# BeatlePad.net
KiCad netlist of a schematic drawn in EAGLE
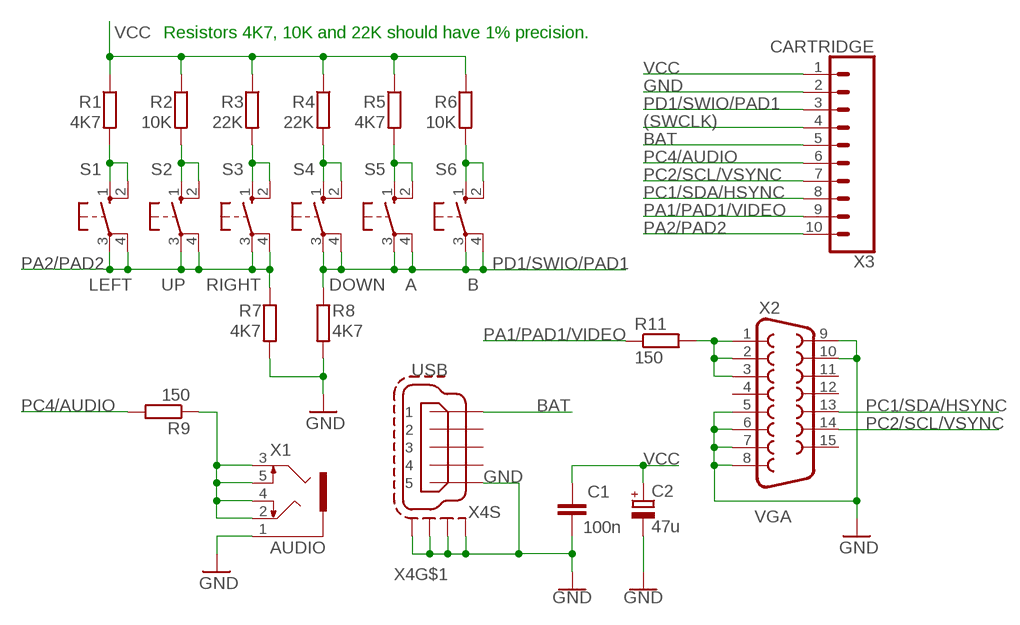
[diagram p0: schematic, sheet 1]

(export (version "E")
  (design (tool "Eeschema 10.0.6"))
  (components
    (comp (ref "C1")
      (value "100n")
      (footprint "eagle-import:C025-024X044")
      (libsource (lib "eagle-import") (part "C-EU025-024X044"))
    )
    (comp (ref "C2")
      (value "47u")
      (footprint "eagle-import:E2-4")
      (libsource (lib "eagle-import") (part "CPOL-EUE2-4"))
    )
    (comp (ref "R1")
      (value "4K7")
      (footprint "eagle-import:0204V")
      (libsource (lib "eagle-import") (part "R-EU_0204/2V"))
    )
    (comp (ref "R2")
      (value "10K")
      (footprint "eagle-import:0204V")
      (libsource (lib "eagle-import") (part "R-EU_0204/2V"))
    )
    (comp (ref "R3")
      (value "22K")
      (footprint "eagle-import:0204V")
      (libsource (lib "eagle-import") (part "R-EU_0204/2V"))
    )
    (comp (ref "R4")
      (value "22K")
      (footprint "eagle-import:0204V")
      (libsource (lib "eagle-import") (part "R-EU_0204/2V"))
    )
    (comp (ref "R5")
      (value "4K7")
      (footprint "eagle-import:0204V")
      (libsource (lib "eagle-import") (part "R-EU_0204/2V"))
    )
    (comp (ref "R6")
      (value "10K")
      (footprint "eagle-import:0204V")
      (libsource (lib "eagle-import") (part "R-EU_0204/2V"))
    )
    (comp (ref "R7")
      (value "4K7")
      (footprint "eagle-import:0204_5")
      (libsource (lib "eagle-import") (part "R-EU_0204/5"))
    )
    (comp (ref "R8")
      (value "4K7")
      (footprint "eagle-import:0204V")
      (libsource (lib "eagle-import") (part "R-EU_0204/2V"))
    )
    (comp (ref "R9")
      (value "150")
      (footprint "eagle-import:0204_5")
      (libsource (lib "eagle-import") (part "R-EU_0204/5"))
    )
    (comp (ref "R11")
      (value "150")
      (footprint "eagle-import:0204_5")
      (libsource (lib "eagle-import") (part "R-EU_0204/5"))
    )
    (comp (ref "S1")
      (value "LEFT")
      (footprint "eagle-import:B3F-10XXB")
      (libsource (lib "eagle-import") (part "10-XXB3F-10XXB"))
    )
    (comp (ref "S2")
      (value "UP")
      (footprint "eagle-import:B3F-10XXB")
      (libsource (lib "eagle-import") (part "10-XXB3F-10XXB"))
    )
    (comp (ref "S3")
      (value "RIGHT")
      (footprint "eagle-import:B3F-10XXB")
      (libsource (lib "eagle-import") (part "10-XXB3F-10XXB"))
    )
    (comp (ref "S4")
      (value "DOWN")
      (footprint "eagle-import:B3F-10XXB")
      (libsource (lib "eagle-import") (part "10-XXB3F-10XXB"))
    )
    (comp (ref "S5")
      (value "A")
      (footprint "eagle-import:B3F-10XXB")
      (libsource (lib "eagle-import") (part "10-XXB3F-10XXB"))
    )
    (comp (ref "S6")
      (value "B")
      (footprint "eagle-import:B3F-10XXB")
      (libsource (lib "eagle-import") (part "10-XXB3F-10XXB"))
    )
    (comp (ref "X1")
      (value "AUDIO")
      (footprint "eagle-import:1503_09")
      (libsource (lib "eagle-import") (part "1503_09"))
    )
    (comp (ref "X2")
      (value "VGA")
      (footprint "eagle-import:HDF15H")
      (libsource (lib "eagle-import") (part "F15HDH"))
    )
    (comp (ref "X3")
      (value "CARTRIDGE")
      (footprint "eagle-import:1X10_LONGPADS")
      (libsource (lib "eagle-import") (part "CONN_10"))
    )
    (comp (ref "X4")
      (value "USB")
      (footprint "eagle-import:32005-201")
      (libsource (lib "eagle-import") (part "MINI-USB-SCHIELD-32005-201"))
    )
  )
  (nets
    (net (code "1") (name "/(SWCLK)") (class "Default")
      (node (ref "X3") (pin "4") (pinfunction "4_4") (pintype "passive"))
    )
    (net (code "2") (name "/BAT") (class "Default")
      (node (ref "X3") (pin "5") (pinfunction "5_5") (pintype "passive"))
      (node (ref "X4") (pin "1") (pinfunction "1_1") (pintype "passive"))
    )
    (net (code "3") (name "/PA1{slash}PAD1{slash}VIDEO") (class "Default")
      (node (ref "R11") (pin "1") (pinfunction "1_1") (pintype "passive"))
      (node (ref "X3") (pin "9") (pinfunction "9_9") (pintype "passive"))
    )
    (net (code "4") (name "/PA2{slash}PAD2") (class "Default")
      (node (ref "R7") (pin "1") (pinfunction "1_1") (pintype "passive"))
      (node (ref "S1") (pin "3") (pinfunction "P_3") (pintype "passive"))
      (node (ref "S1") (pin "4") (pinfunction "P1_4") (pintype "passive"))
      (node (ref "S2") (pin "3") (pinfunction "P_3") (pintype "passive"))
      (node (ref "S2") (pin "4") (pinfunction "P1_4") (pintype "passive"))
      (node (ref "S3") (pin "3") (pinfunction "P_3") (pintype "passive"))
      (node (ref "S3") (pin "4") (pinfunction "P1_4") (pintype "passive"))
      (node (ref "X3") (pin "10") (pinfunction "10_10") (pintype "passive"))
    )
    (net (code "5") (name "/PC1{slash}SDA{slash}HSYNC") (class "Default")
      (node (ref "X2") (pin "13") (pinfunction "13_13") (pintype "passive"))
      (node (ref "X3") (pin "8") (pinfunction "8_8") (pintype "passive"))
    )
    (net (code "6") (name "/PC2{slash}SCL{slash}VSYNC") (class "Default")
      (node (ref "X2") (pin "14") (pinfunction "14_14") (pintype "passive"))
      (node (ref "X3") (pin "7") (pinfunction "7_7") (pintype "passive"))
    )
    (net (code "7") (name "/PC4{slash}AUDIO") (class "Default")
      (node (ref "R9") (pin "2") (pinfunction "2_2") (pintype "passive"))
      (node (ref "X3") (pin "6") (pinfunction "6_6") (pintype "passive"))
    )
    (net (code "8") (name "/PD1{slash}SWIO{slash}PAD1") (class "Default")
      (node (ref "R8") (pin "1") (pinfunction "1_1") (pintype "passive"))
      (node (ref "S4") (pin "3") (pinfunction "P_3") (pintype "passive"))
      (node (ref "S4") (pin "4") (pinfunction "P1_4") (pintype "passive"))
      (node (ref "S5") (pin "3") (pinfunction "P_3") (pintype "passive"))
      (node (ref "S5") (pin "4") (pinfunction "P1_4") (pintype "passive"))
      (node (ref "S6") (pin "3") (pinfunction "P_3") (pintype "passive"))
      (node (ref "S6") (pin "4") (pinfunction "P1_4") (pintype "passive"))
      (node (ref "X3") (pin "3") (pinfunction "3_3") (pintype "passive"))
    )
    (net (code "9") (name "/VCC") (class "Default")
      (node (ref "C1") (pin "1") (pinfunction "1_1") (pintype "passive"))
      (node (ref "C2") (pin "+") (pinfunction "+_+") (pintype "passive"))
      (node (ref "R1") (pin "1") (pinfunction "1_1") (pintype "passive"))
      (node (ref "R2") (pin "1") (pinfunction "1_1") (pintype "passive"))
      (node (ref "R3") (pin "1") (pinfunction "1_1") (pintype "passive"))
      (node (ref "R4") (pin "1") (pinfunction "1_1") (pintype "passive"))
      (node (ref "R5") (pin "1") (pinfunction "1_1") (pintype "passive"))
      (node (ref "R6") (pin "1") (pinfunction "1_1") (pintype "passive"))
      (node (ref "X3") (pin "1") (pinfunction "1_1") (pintype "passive"))
    )
    (net (code "10") (name "GND") (class "Default")
      (node (ref "C1") (pin "2") (pinfunction "2_2") (pintype "passive"))
      (node (ref "C2") (pin "-") (pinfunction "-_-") (pintype "passive"))
      (node (ref "R7") (pin "2") (pinfunction "2_2") (pintype "passive"))
      (node (ref "R8") (pin "2") (pinfunction "2_2") (pintype "passive"))
      (node (ref "X1") (pin "1") (pinfunction "1_1") (pintype "passive"))
      (node (ref "X2") (pin "10") (pinfunction "10_10") (pintype "passive"))
      (node (ref "X2") (pin "5") (pinfunction "5_5") (pintype "passive"))
      (node (ref "X2") (pin "6") (pinfunction "6_6") (pintype "passive"))
      (node (ref "X2") (pin "7") (pinfunction "7_7") (pintype "passive"))
      (node (ref "X2") (pin "8") (pinfunction "8_8") (pintype "passive"))
      (node (ref "X2") (pin "9") (pinfunction "9_9") (pintype "passive"))
      (node (ref "X3") (pin "2") (pinfunction "2_2") (pintype "passive"))
      (node (ref "X4") (pin "5") (pinfunction "5_5") (pintype "passive"))
      (node (ref "X4") (pin "M1") (pinfunction "S1_M1") (pintype "passive"))
      (node (ref "X4") (pin "M2") (pinfunction "S2_M2") (pintype "passive"))
      (node (ref "X4") (pin "M3") (pinfunction "S3_M3") (pintype "passive"))
      (node (ref "X4") (pin "M4") (pinfunction "S4_M4") (pintype "passive"))
    )
    (net (code "11") (name "Net-(R9-Pad1)") (class "Default")
      (node (ref "R9") (pin "1") (pinfunction "1_1") (pintype "passive"))
      (node (ref "X1") (pin "2") (pinfunction "2_2") (pintype "passive"))
      (node (ref "X1") (pin "3") (pinfunction "3_3") (pintype "passive"))
      (node (ref "X1") (pin "4") (pinfunction "4_4") (pintype "passive"))
      (node (ref "X1") (pin "5") (pinfunction "5_5") (pintype "passive"))
    )
    (net (code "12") (name "Net-(R11-Pad2)") (class "Default")
      (node (ref "R11") (pin "2") (pinfunction "2_2") (pintype "passive"))
      (node (ref "X2") (pin "1") (pinfunction "1_1") (pintype "passive"))
      (node (ref "X2") (pin "2") (pinfunction "2_2") (pintype "passive"))
      (node (ref "X2") (pin "3") (pinfunction "3_3") (pintype "passive"))
    )
    (net (code "13") (name "Net-(S1-S)") (class "Default")
      (node (ref "R1") (pin "2") (pinfunction "2_2") (pintype "passive"))
      (node (ref "S1") (pin "1") (pinfunction "S_1") (pintype "passive"))
      (node (ref "S1") (pin "2") (pinfunction "S1_2") (pintype "passive"))
    )
    (net (code "14") (name "Net-(S2-S)") (class "Default")
      (node (ref "R2") (pin "2") (pinfunction "2_2") (pintype "passive"))
      (node (ref "S2") (pin "1") (pinfunction "S_1") (pintype "passive"))
      (node (ref "S2") (pin "2") (pinfunction "S1_2") (pintype "passive"))
    )
    (net (code "15") (name "Net-(S3-S)") (class "Default")
      (node (ref "R3") (pin "2") (pinfunction "2_2") (pintype "passive"))
      (node (ref "S3") (pin "1") (pinfunction "S_1") (pintype "passive"))
      (node (ref "S3") (pin "2") (pinfunction "S1_2") (pintype "passive"))
    )
    (net (code "16") (name "Net-(S4-S)") (class "Default")
      (node (ref "R4") (pin "2") (pinfunction "2_2") (pintype "passive"))
      (node (ref "S4") (pin "1") (pinfunction "S_1") (pintype "passive"))
      (node (ref "S4") (pin "2") (pinfunction "S1_2") (pintype "passive"))
    )
    (net (code "17") (name "Net-(S5-S)") (class "Default")
      (node (ref "R5") (pin "2") (pinfunction "2_2") (pintype "passive"))
      (node (ref "S5") (pin "1") (pinfunction "S_1") (pintype "passive"))
      (node (ref "S5") (pin "2") (pinfunction "S1_2") (pintype "passive"))
    )
    (net (code "18") (name "Net-(S6-S)") (class "Default")
      (node (ref "R6") (pin "2") (pinfunction "2_2") (pintype "passive"))
      (node (ref "S6") (pin "1") (pinfunction "S_1") (pintype "passive"))
      (node (ref "S6") (pin "2") (pinfunction "S1_2") (pintype "passive"))
    )
    (net (code "19") (name "unconnected-(X2-Pad4)") (class "Default")
      (node (ref "X2") (pin "4") (pinfunction "4_4") (pintype "passive"))
    )
    (net (code "20") (name "unconnected-(X2-Pad11)") (class "Default")
      (node (ref "X2") (pin "11") (pinfunction "11_11") (pintype "passive"))
    )
    (net (code "21") (name "unconnected-(X2-Pad12)") (class "Default")
      (node (ref "X2") (pin "12") (pinfunction "12_12") (pintype "passive"))
    )
    (net (code "22") (name "unconnected-(X2-Pad15)") (class "Default")
      (node (ref "X2") (pin "15") (pinfunction "15_15") (pintype "passive"))
    )
    (net (code "23") (name "unconnected-(X4-Pad2)") (class "Default")
      (node (ref "X4") (pin "2") (pinfunction "2_2") (pintype "passive"))
    )
    (net (code "24") (name "unconnected-(X4-Pad3)") (class "Default")
      (node (ref "X4") (pin "3") (pinfunction "3_3") (pintype "passive"))
    )
    (net (code "25") (name "unconnected-(X4-Pad4)") (class "Default")
      (node (ref "X4") (pin "4") (pinfunction "4_4") (pintype "passive"))
    )
  )
)
